# FT232.net
KiCad netlist of a schematic drawn in EAGLE
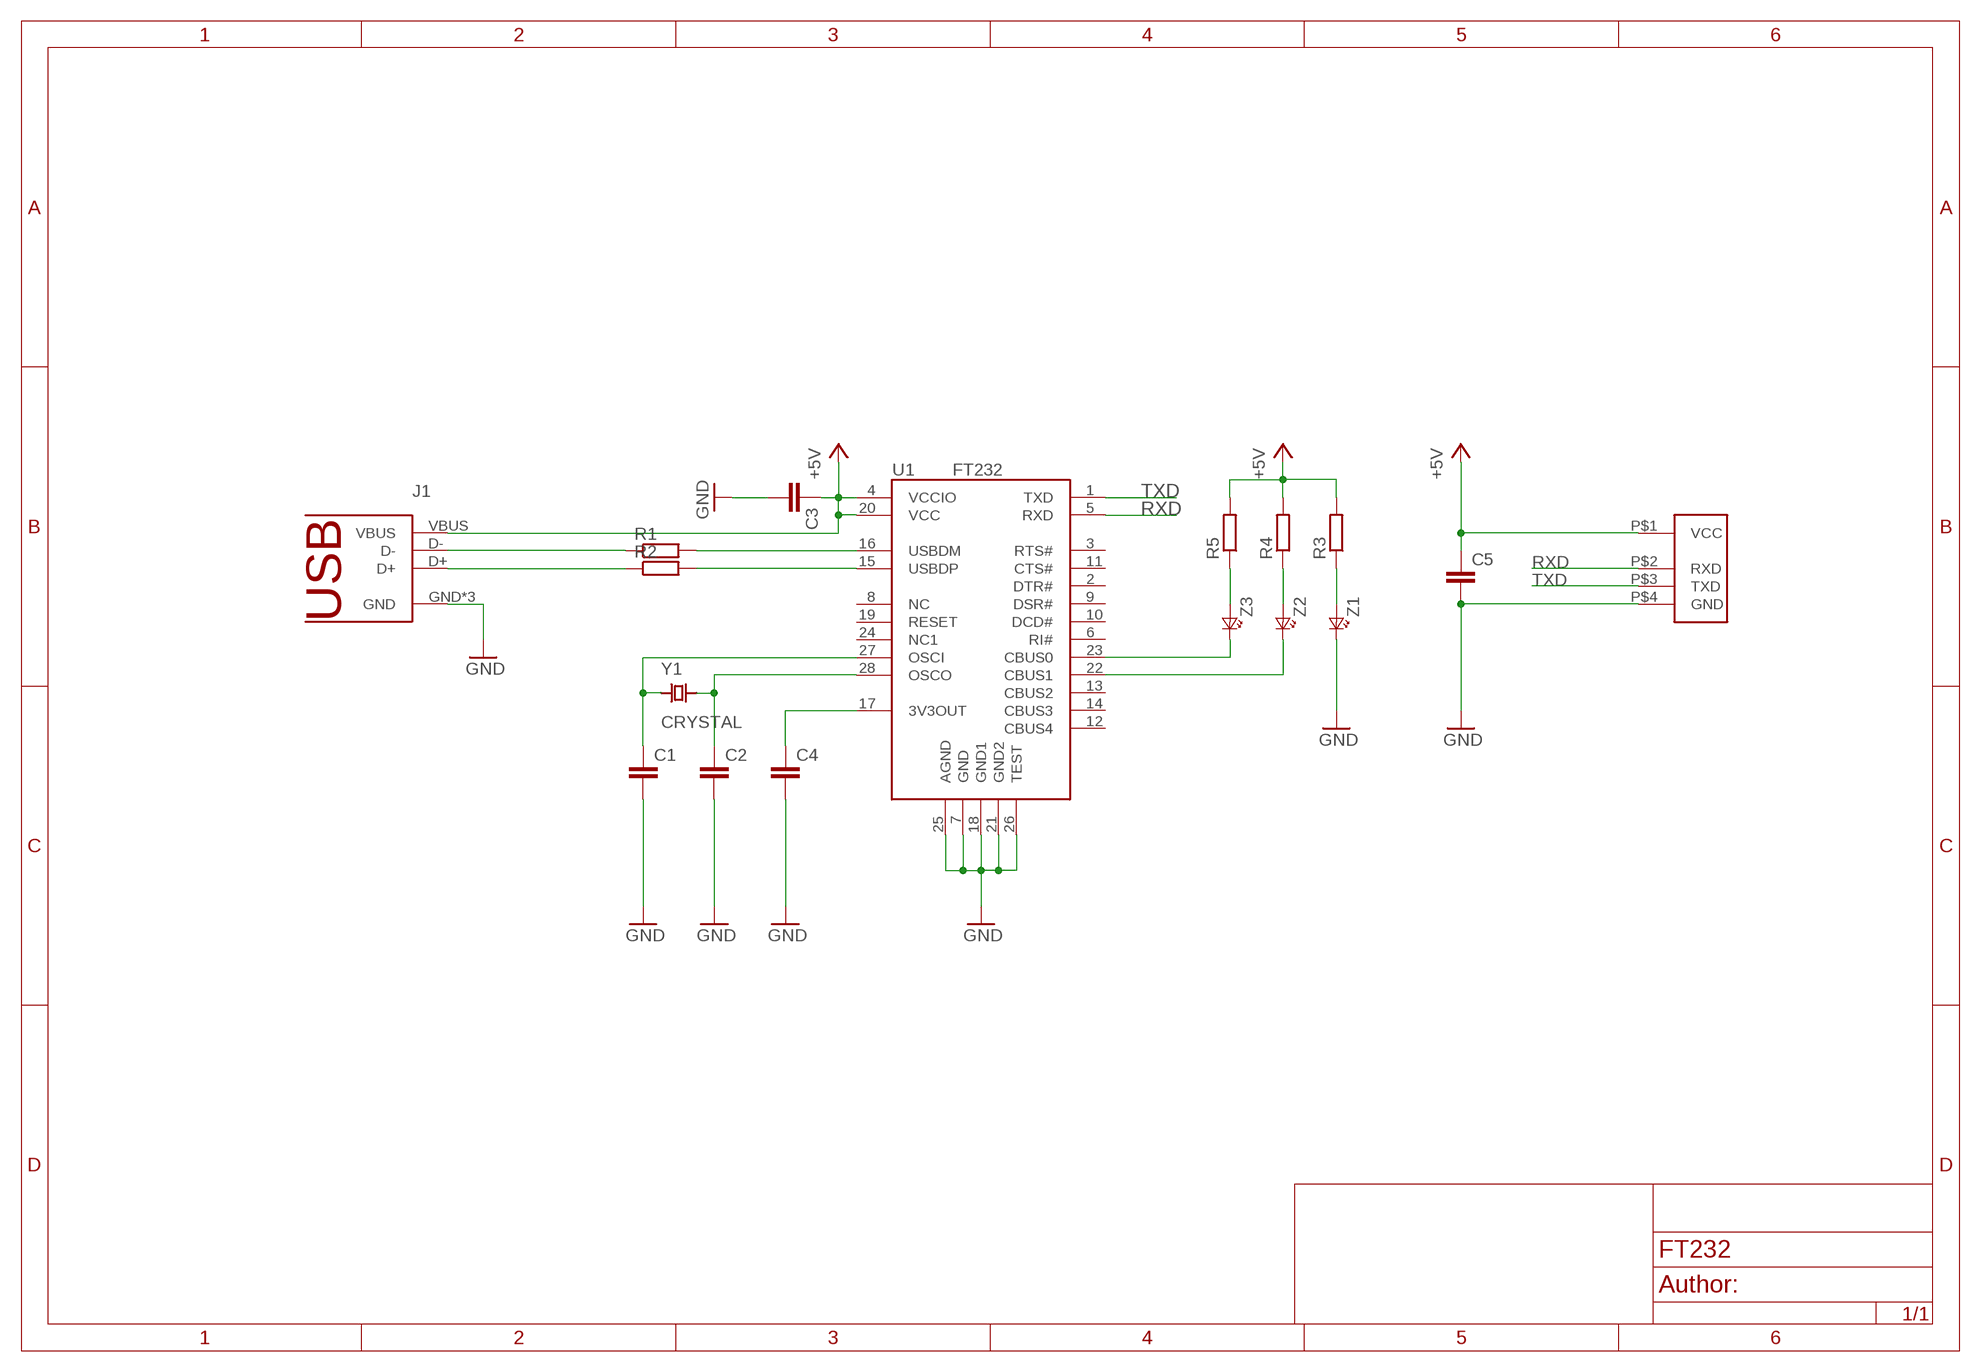
[diagram p0: schematic, sheet 1]

(export (version "E")
  (design (tool "Eeschema 10.0.6"))
  (components
    (comp (ref "C1")
      (value "CAPACITOR0402")
      (footprint "eagle-import:C0402")
      (libsource (lib "eagle-import") (part "CAPACITOR0402"))
    )
    (comp (ref "C2")
      (value "CAPACITOR0402")
      (footprint "eagle-import:C0402")
      (libsource (lib "eagle-import") (part "CAPACITOR0402"))
    )
    (comp (ref "C3")
      (value "CAPACITOR0402")
      (footprint "eagle-import:C0402")
      (libsource (lib "eagle-import") (part "CAPACITOR0402"))
    )
    (comp (ref "C4")
      (value "CAPACITOR0402")
      (footprint "eagle-import:C0402")
      (libsource (lib "eagle-import") (part "CAPACITOR0402"))
    )
    (comp (ref "C5")
      (value "CAPACITOR0402")
      (footprint "eagle-import:C0402")
      (libsource (lib "eagle-import") (part "CAPACITOR0402"))
    )
    (comp (ref "J1")
      (value "USBA")
      (footprint "eagle-import:USB_A")
      (libsource (lib "eagle-import") (part "USBA"))
    )
    (comp (ref "J2")
      (value "CON")
      (footprint "eagle-import:CON4")
      (libsource (lib "eagle-import") (part "CON"))
    )
    (comp (ref "R1")
      (value "RESISTOR0402")
      (footprint "eagle-import:R0402")
      (libsource (lib "eagle-import") (part "RESISTOR0402"))
    )
    (comp (ref "R2")
      (value "RESISTOR0402")
      (footprint "eagle-import:R0402")
      (libsource (lib "eagle-import") (part "RESISTOR0402"))
    )
    (comp (ref "R3")
      (value "RESISTOR0402")
      (footprint "eagle-import:R0402")
      (libsource (lib "eagle-import") (part "RESISTOR0402"))
    )
    (comp (ref "R4")
      (value "RESISTOR0402")
      (footprint "eagle-import:R0402")
      (libsource (lib "eagle-import") (part "RESISTOR0402"))
    )
    (comp (ref "R5")
      (value "RESISTOR0402")
      (footprint "eagle-import:R0402")
      (libsource (lib "eagle-import") (part "RESISTOR0402"))
    )
    (comp (ref "U1")
      (value "FT232")
      (footprint "eagle-import:SSOP28")
      (libsource (lib "eagle-import") (part "FT232"))
    )
    (comp (ref "Y1")
      (value "CRYSTAL")
      (footprint "eagle-import:CRYSTAL5032")
      (libsource (lib "eagle-import") (part "CRYSTAL"))
    )
    (comp (ref "Z1")
      (value "LED")
      (footprint "eagle-import:LED0805")
      (libsource (lib "eagle-import") (part "LED"))
    )
    (comp (ref "Z2")
      (value "LED")
      (footprint "eagle-import:LED0805")
      (libsource (lib "eagle-import") (part "LED"))
    )
    (comp (ref "Z3")
      (value "LED")
      (footprint "eagle-import:LED0805")
      (libsource (lib "eagle-import") (part "LED"))
    )
  )
  (nets
    (net (code "1") (name "+5V") (class "Default")
      (node (ref "C3") (pin "1") (pinfunction "1_1") (pintype "passive"))
      (node (ref "C5") (pin "1") (pinfunction "1_1") (pintype "passive"))
      (node (ref "J1") (pin "VBUS") (pinfunction "VBUS_VBUS") (pintype "power_in"))
      (node (ref "J2") (pin "P$1") (pinfunction "VCC_P$1") (pintype "bidirectional"))
      (node (ref "R3") (pin "2") (pinfunction "2_2") (pintype "passive"))
      (node (ref "R4") (pin "2") (pinfunction "2_2") (pintype "passive"))
      (node (ref "R5") (pin "2") (pinfunction "2_2") (pintype "passive"))
      (node (ref "U1") (pin "20") (pinfunction "VCC_20") (pintype "power_in"))
      (node (ref "U1") (pin "4") (pinfunction "VCCIO_4") (pintype "power_in"))
    )
    (net (code "2") (name "/RXD") (class "Default")
      (node (ref "J2") (pin "P$2") (pinfunction "RXD_P$2") (pintype "bidirectional"))
      (node (ref "U1") (pin "5") (pinfunction "RXD_5") (pintype "bidirectional"))
    )
    (net (code "3") (name "/TXD") (class "Default")
      (node (ref "J2") (pin "P$3") (pinfunction "TXD_P$3") (pintype "bidirectional"))
      (node (ref "U1") (pin "1") (pinfunction "TXD_1") (pintype "bidirectional"))
    )
    (net (code "4") (name "GND") (class "Default")
      (node (ref "C1") (pin "2") (pinfunction "2_2") (pintype "passive"))
      (node (ref "C2") (pin "2") (pinfunction "2_2") (pintype "passive"))
      (node (ref "C3") (pin "2") (pinfunction "2_2") (pintype "passive"))
      (node (ref "C4") (pin "2") (pinfunction "2_2") (pintype "passive"))
      (node (ref "C5") (pin "2") (pinfunction "2_2") (pintype "passive"))
      (node (ref "J1") (pin "GND") (pinfunction "GND_GND") (pintype "power_in"))
      (node (ref "J1") (pin "GND1") (pinfunction "GND_GND1") (pintype "power_in"))
      (node (ref "J1") (pin "GND2") (pinfunction "GND_GND2") (pintype "power_in"))
      (node (ref "J2") (pin "P$4") (pinfunction "GND_P$4") (pintype "bidirectional"))
      (node (ref "U1") (pin "18") (pinfunction "GND1_18") (pintype "power_in"))
      (node (ref "U1") (pin "21") (pinfunction "GND2_21") (pintype "power_in"))
      (node (ref "U1") (pin "25") (pinfunction "AGND_25") (pintype "power_in"))
      (node (ref "U1") (pin "26") (pinfunction "TEST_26") (pintype "bidirectional"))
      (node (ref "U1") (pin "7") (pinfunction "GND_7") (pintype "power_in"))
      (node (ref "Z1") (pin "K") (pinfunction "K_K") (pintype "output"))
    )
    (net (code "5") (name "Net-(J1-PadD+)") (class "Default")
      (node (ref "J1") (pin "D+") (pinfunction "D+_D+") (pintype "bidirectional"))
      (node (ref "R2") (pin "1") (pinfunction "1_1") (pintype "passive"))
    )
    (net (code "6") (name "Net-(J1-PadD-)") (class "Default")
      (node (ref "J1") (pin "D-") (pinfunction "D-_D-") (pintype "bidirectional"))
      (node (ref "R1") (pin "1") (pinfunction "1_1") (pintype "passive"))
    )
    (net (code "7") (name "Net-(R3-Pad1)") (class "Default")
      (node (ref "R3") (pin "1") (pinfunction "1_1") (pintype "passive"))
      (node (ref "Z1") (pin "A") (pinfunction "A_A") (pintype "input"))
    )
    (net (code "8") (name "Net-(R4-Pad1)") (class "Default")
      (node (ref "R4") (pin "1") (pinfunction "1_1") (pintype "passive"))
      (node (ref "Z2") (pin "A") (pinfunction "A_A") (pintype "input"))
    )
    (net (code "9") (name "Net-(R5-Pad1)") (class "Default")
      (node (ref "R5") (pin "1") (pinfunction "1_1") (pintype "passive"))
      (node (ref "Z3") (pin "A") (pinfunction "A_A") (pintype "input"))
    )
    (net (code "10") (name "Net-(U1-3V3OUT)") (class "Default")
      (node (ref "C4") (pin "1") (pinfunction "1_1") (pintype "passive"))
      (node (ref "U1") (pin "17") (pinfunction "3V3OUT_17") (pintype "output"))
    )
    (net (code "11") (name "Net-(U1-CBUS0)") (class "Default")
      (node (ref "U1") (pin "23") (pinfunction "CBUS0_23") (pintype "bidirectional"))
      (node (ref "Z3") (pin "K") (pinfunction "K_K") (pintype "output"))
    )
    (net (code "12") (name "Net-(U1-CBUS1)") (class "Default")
      (node (ref "U1") (pin "22") (pinfunction "CBUS1_22") (pintype "bidirectional"))
      (node (ref "Z2") (pin "K") (pinfunction "K_K") (pintype "output"))
    )
    (net (code "13") (name "Net-(U1-OSCI)") (class "Default")
      (node (ref "C1") (pin "1") (pinfunction "1_1") (pintype "passive"))
      (node (ref "U1") (pin "27") (pinfunction "OSCI_27") (pintype "bidirectional"))
      (node (ref "Y1") (pin "1") (pinfunction "P$1_1") (pintype "passive"))
    )
    (net (code "14") (name "Net-(U1-OSCO)") (class "Default")
      (node (ref "C2") (pin "1") (pinfunction "1_1") (pintype "passive"))
      (node (ref "U1") (pin "28") (pinfunction "OSCO_28") (pintype "bidirectional"))
      (node (ref "Y1") (pin "2") (pinfunction "P$2_2") (pintype "passive"))
    )
    (net (code "15") (name "Net-(U1-USBDM)") (class "Default")
      (node (ref "R1") (pin "2") (pinfunction "2_2") (pintype "passive"))
      (node (ref "U1") (pin "16") (pinfunction "USBDM_16") (pintype "bidirectional"))
    )
    (net (code "16") (name "Net-(U1-USBDP)") (class "Default")
      (node (ref "R2") (pin "2") (pinfunction "2_2") (pintype "passive"))
      (node (ref "U1") (pin "15") (pinfunction "USBDP_15") (pintype "bidirectional"))
    )
    (net (code "17") (name "unconnected-(U1-CBUS2-Pad13)") (class "Default")
      (node (ref "U1") (pin "13") (pinfunction "CBUS2_13") (pintype "bidirectional"))
    )
    (net (code "18") (name "unconnected-(U1-CBUS3-Pad14)") (class "Default")
      (node (ref "U1") (pin "14") (pinfunction "CBUS3_14") (pintype "bidirectional"))
    )
    (net (code "19") (name "unconnected-(U1-CBUS4-Pad12)") (class "Default")
      (node (ref "U1") (pin "12") (pinfunction "CBUS4_12") (pintype "bidirectional"))
    )
    (net (code "20") (name "unconnected-(U1-CTS#-Pad11)") (class "Default")
      (node (ref "U1") (pin "11") (pinfunction "CTS#_11") (pintype "bidirectional"))
    )
    (net (code "21") (name "unconnected-(U1-DCD#-Pad10)") (class "Default")
      (node (ref "U1") (pin "10") (pinfunction "DCD#_10") (pintype "bidirectional"))
    )
    (net (code "22") (name "unconnected-(U1-DSR#-Pad9)") (class "Default")
      (node (ref "U1") (pin "9") (pinfunction "DSR#_9") (pintype "bidirectional"))
    )
    (net (code "23") (name "unconnected-(U1-DTR#-Pad2)") (class "Default")
      (node (ref "U1") (pin "2") (pinfunction "DTR#_2") (pintype "bidirectional"))
    )
    (net (code "24") (name "unconnected-(U1-NC-Pad8)") (class "Default")
      (node (ref "U1") (pin "8") (pinfunction "NC_8") (pintype "bidirectional"))
    )
    (net (code "25") (name "unconnected-(U1-NC1-Pad24)") (class "Default")
      (node (ref "U1") (pin "24") (pinfunction "NC1_24") (pintype "bidirectional"))
    )
    (net (code "26") (name "unconnected-(U1-RESET-Pad19)") (class "Default")
      (node (ref "U1") (pin "19") (pinfunction "RESET_19") (pintype "bidirectional"))
    )
    (net (code "27") (name "unconnected-(U1-RI#-Pad6)") (class "Default")
      (node (ref "U1") (pin "6") (pinfunction "RI#_6") (pintype "bidirectional"))
    )
    (net (code "28") (name "unconnected-(U1-RTS#-Pad3)") (class "Default")
      (node (ref "U1") (pin "3") (pinfunction "RTS#_3") (pintype "bidirectional"))
    )
  )
)
